# amp_interface_v_1_0.net
KiCad netlist of a schematic drawn in EAGLE
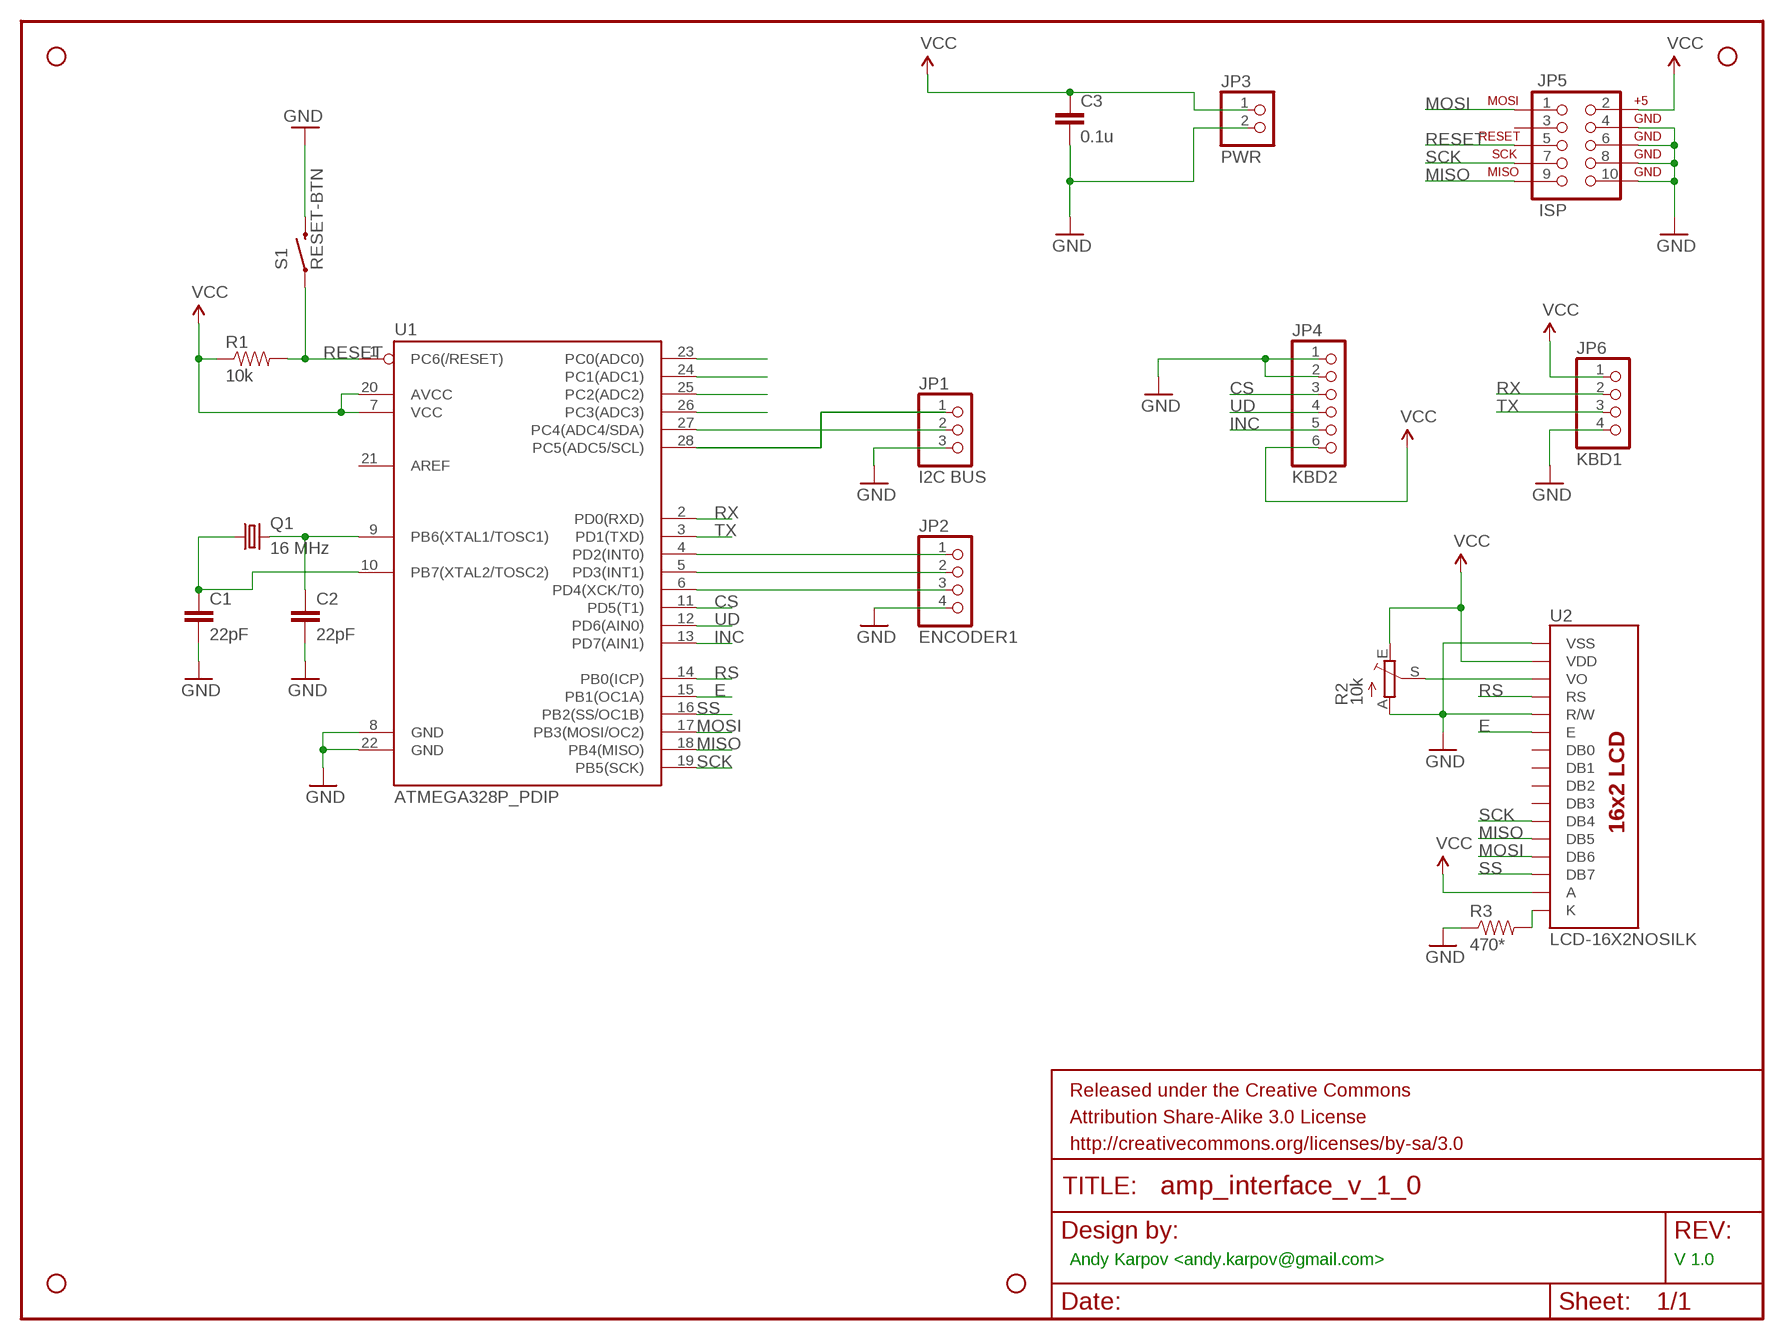
[diagram p0: schematic, sheet 1]

(export (version "E")
  (design (tool "Eeschema 10.0.6"))
  (components
    (comp (ref "C1")
      (value "22pF")
      (footprint "eagle-import:CAP-PTH-SMALL2")
      (libsource (lib "eagle-import") (part "CAPPTH2"))
    )
    (comp (ref "C2")
      (value "22pF")
      (footprint "eagle-import:CAP-PTH-SMALL2")
      (libsource (lib "eagle-import") (part "CAPPTH2"))
    )
    (comp (ref "C3")
      (value "0.1u")
      (footprint "eagle-import:CAP-PTH-SMALL2")
      (libsource (lib "eagle-import") (part "CAPPTH2"))
    )
    (comp (ref "FRAME1")
      (value "FRAME-LETTER")
      (footprint "eagle-import:CREATIVE_COMMONS")
      (libsource (lib "eagle-import") (part "FRAME-LETTER"))
    )
    (comp (ref "JP1")
      (value "I2C BUS")
      (footprint "eagle-import:1X03")
      (libsource (lib "eagle-import") (part "PINHD-1X3"))
    )
    (comp (ref "JP2")
      (value "ENCODER1")
      (footprint "eagle-import:1X04")
      (libsource (lib "eagle-import") (part "PINHD-1X4"))
    )
    (comp (ref "JP3")
      (value "PWR")
      (footprint "eagle-import:1X02")
      (libsource (lib "eagle-import") (part "PINHD-1X2"))
    )
    (comp (ref "JP4")
      (value "KBD2")
      (footprint "eagle-import:1X06")
      (libsource (lib "eagle-import") (part "PINHD-1X6"))
    )
    (comp (ref "JP5")
      (value "ISP")
      (footprint "eagle-import:2X5-SHROUDED")
      (libsource (lib "eagle-import") (part "AVR_SPI_PROG2PTH2"))
    )
    (comp (ref "JP6")
      (value "KBD1")
      (footprint "eagle-import:1X04")
      (libsource (lib "eagle-import") (part "PINHD-1X4"))
    )
    (comp (ref "Q1")
      (value "16 MHz")
      (footprint "eagle-import:HC49_S")
      (libsource (lib "eagle-import") (part "CRYSTALHC49S"))
    )
    (comp (ref "R1")
      (value "10k")
      (footprint "eagle-import:AXIAL-0.4")
      (libsource (lib "eagle-import") (part "RESISTORPTH-1/4W"))
    )
    (comp (ref "R2")
      (value "10k")
      (footprint "eagle-import:B64Y")
      (libsource (lib "eagle-import") (part "TRIM_EU-B64Y"))
    )
    (comp (ref "R3")
      (value "470*")
      (footprint "eagle-import:AXIAL-0.4")
      (libsource (lib "eagle-import") (part "RESISTORPTH-1/4W"))
    )
    (comp (ref "S1")
      (value "RESET-BTN")
      (footprint "eagle-import:TACTILE-PTH")
      (libsource (lib "eagle-import") (part "SWITCH-MOMENTARY-2PTH"))
    )
    (comp (ref "STANDOFF1")
      (value "STAND-OFF")
      (footprint "eagle-import:STAND-OFF")
      (libsource (lib "eagle-import") (part "STAND-OFF"))
    )
    (comp (ref "STANDOFF2")
      (value "STAND-OFF")
      (footprint "eagle-import:STAND-OFF")
      (libsource (lib "eagle-import") (part "STAND-OFF"))
    )
    (comp (ref "STANDOFF3")
      (value "STAND-OFF")
      (footprint "eagle-import:STAND-OFF")
      (libsource (lib "eagle-import") (part "STAND-OFF"))
    )
    (comp (ref "STANDOFF4")
      (value "STAND-OFF")
      (footprint "eagle-import:STAND-OFF")
      (libsource (lib "eagle-import") (part "STAND-OFF"))
    )
    (comp (ref "U1")
      (value "ATMEGA328P_PDIP")
      (footprint "eagle-import:DIL28-3")
      (libsource (lib "eagle-import") (part "ATMEGA328P_PDIP"))
    )
    (comp (ref "U2")
      (value "LCD-16X2NOSILK")
      (footprint "eagle-import:LCD-16X2_NOSILK")
      (libsource (lib "eagle-import") (part "LCD-16X2NOSILK"))
    )
  )
  (nets
    (net (code "1") (name "/CS") (class "Default")
      (node (ref "JP4") (pin "3") (pinfunction "3_3") (pintype "passive"))
      (node (ref "U1") (pin "11") (pinfunction "PD5(T1)_11") (pintype "bidirectional"))
    )
    (net (code "2") (name "/E") (class "Default")
      (node (ref "U1") (pin "15") (pinfunction "PB1(OC1A)_15") (pintype "bidirectional"))
      (node (ref "U2") (pin "6") (pinfunction "E_6") (pintype "input"))
    )
    (net (code "3") (name "/INC") (class "Default")
      (node (ref "JP4") (pin "5") (pinfunction "5_5") (pintype "passive"))
      (node (ref "U1") (pin "13") (pinfunction "PD7(AIN1)_13") (pintype "bidirectional"))
    )
    (net (code "4") (name "/MISO") (class "Default")
      (node (ref "JP5") (pin "9") (pinfunction "9_9") (pintype "passive"))
      (node (ref "U1") (pin "18") (pinfunction "PB4(MISO)_18") (pintype "bidirectional"))
      (node (ref "U2") (pin "12") (pinfunction "DB5_12") (pintype "bidirectional"))
    )
    (net (code "5") (name "/MOSI") (class "Default")
      (node (ref "JP5") (pin "1") (pinfunction "1_1") (pintype "passive"))
      (node (ref "U1") (pin "17") (pinfunction "PB3(MOSI/OC2)_17") (pintype "bidirectional"))
      (node (ref "U2") (pin "13") (pinfunction "DB6_13") (pintype "bidirectional"))
    )
    (net (code "6") (name "/RESET") (class "Default")
      (node (ref "JP5") (pin "5") (pinfunction "5_5") (pintype "passive"))
      (node (ref "R1") (pin "P$2") (pinfunction "2_P$2") (pintype "passive"))
      (node (ref "S1") (pin "1") (pinfunction "1_1") (pintype "passive"))
      (node (ref "U1") (pin "1") (pinfunction "PC6(/RESET)_1") (pintype "bidirectional"))
    )
    (net (code "7") (name "/RS") (class "Default")
      (node (ref "U1") (pin "14") (pinfunction "PB0(ICP)_14") (pintype "bidirectional"))
      (node (ref "U2") (pin "4") (pinfunction "RS_4") (pintype "input"))
    )
    (net (code "8") (name "/RX") (class "Default")
      (node (ref "JP6") (pin "2") (pinfunction "2_2") (pintype "passive"))
      (node (ref "U1") (pin "2") (pinfunction "PD0(RXD)_2") (pintype "bidirectional"))
    )
    (net (code "9") (name "/SCK") (class "Default")
      (node (ref "JP5") (pin "7") (pinfunction "7_7") (pintype "passive"))
      (node (ref "U1") (pin "19") (pinfunction "PB5(SCK)_19") (pintype "bidirectional"))
      (node (ref "U2") (pin "11") (pinfunction "DB4_11") (pintype "bidirectional"))
    )
    (net (code "10") (name "/SS") (class "Default")
      (node (ref "U1") (pin "16") (pinfunction "PB2(SS/OC1B)_16") (pintype "bidirectional"))
      (node (ref "U2") (pin "14") (pinfunction "DB7_14") (pintype "bidirectional"))
    )
    (net (code "11") (name "/TX") (class "Default")
      (node (ref "JP6") (pin "3") (pinfunction "3_3") (pintype "passive"))
      (node (ref "U1") (pin "3") (pinfunction "PD1(TXD)_3") (pintype "bidirectional"))
    )
    (net (code "12") (name "/UD") (class "Default")
      (node (ref "JP4") (pin "4") (pinfunction "4_4") (pintype "passive"))
      (node (ref "U1") (pin "12") (pinfunction "PD6(AIN0)_12") (pintype "bidirectional"))
    )
    (net (code "13") (name "GND") (class "Default")
      (node (ref "C1") (pin "2") (pinfunction "2_2") (pintype "passive"))
      (node (ref "C2") (pin "2") (pinfunction "2_2") (pintype "passive"))
      (node (ref "C3") (pin "2") (pinfunction "2_2") (pintype "passive"))
      (node (ref "JP1") (pin "3") (pinfunction "3_3") (pintype "passive"))
      (node (ref "JP2") (pin "4") (pinfunction "4_4") (pintype "passive"))
      (node (ref "JP3") (pin "2") (pinfunction "2_2") (pintype "passive"))
      (node (ref "JP4") (pin "1") (pinfunction "1_1") (pintype "passive"))
      (node (ref "JP4") (pin "2") (pinfunction "2_2") (pintype "passive"))
      (node (ref "JP5") (pin "10") (pinfunction "10_10") (pintype "passive"))
      (node (ref "JP5") (pin "4") (pinfunction "4_4") (pintype "passive"))
      (node (ref "JP5") (pin "6") (pinfunction "6_6") (pintype "passive"))
      (node (ref "JP5") (pin "8") (pinfunction "8_8") (pintype "passive"))
      (node (ref "JP6") (pin "4") (pinfunction "4_4") (pintype "passive"))
      (node (ref "R2") (pin "A") (pinfunction "A_A") (pintype "passive"))
      (node (ref "R3") (pin "P$1") (pinfunction "1_P$1") (pintype "passive"))
      (node (ref "S1") (pin "3") (pinfunction "2_3") (pintype "passive"))
      (node (ref "U1") (pin "22") (pinfunction "GND_22") (pintype "bidirectional"))
      (node (ref "U1") (pin "8") (pinfunction "GND_8") (pintype "bidirectional"))
      (node (ref "U2") (pin "1") (pinfunction "VSS_1") (pintype "power_in"))
      (node (ref "U2") (pin "5") (pinfunction "R/W_5") (pintype "input"))
    )
    (net (code "14") (name "Net-(R3-2)") (class "Default")
      (node (ref "R3") (pin "P$2") (pinfunction "2_P$2") (pintype "passive"))
      (node (ref "U2") (pin "16") (pinfunction "K_16") (pintype "power_in"))
    )
    (net (code "15") (name "Net-(U1-PB6(XTAL1{slash}TOSC1))") (class "Default")
      (node (ref "C2") (pin "1") (pinfunction "1_1") (pintype "passive"))
      (node (ref "Q1") (pin "2") (pinfunction "2_2") (pintype "passive"))
      (node (ref "U1") (pin "9") (pinfunction "PB6(XTAL1/TOSC1)_9") (pintype "bidirectional"))
    )
    (net (code "16") (name "Net-(U1-PB7(XTAL2{slash}TOSC2))") (class "Default")
      (node (ref "C1") (pin "1") (pinfunction "1_1") (pintype "passive"))
      (node (ref "Q1") (pin "1") (pinfunction "1_1") (pintype "passive"))
      (node (ref "U1") (pin "10") (pinfunction "PB7(XTAL2/TOSC2)_10") (pintype "bidirectional"))
    )
    (net (code "17") (name "Net-(U1-PC4(ADC4{slash}SDA))") (class "Default")
      (node (ref "JP1") (pin "2") (pinfunction "2_2") (pintype "passive"))
      (node (ref "U1") (pin "27") (pinfunction "PC4(ADC4/SDA)_27") (pintype "bidirectional"))
    )
    (net (code "18") (name "Net-(U1-PC5(ADC5{slash}SCL))") (class "Default")
      (node (ref "JP1") (pin "1") (pinfunction "1_1") (pintype "passive"))
      (node (ref "U1") (pin "28") (pinfunction "PC5(ADC5/SCL)_28") (pintype "bidirectional"))
    )
    (net (code "19") (name "Net-(U1-PD2(INT0))") (class "Default")
      (node (ref "JP2") (pin "1") (pinfunction "1_1") (pintype "passive"))
      (node (ref "U1") (pin "4") (pinfunction "PD2(INT0)_4") (pintype "bidirectional"))
    )
    (net (code "20") (name "Net-(U1-PD3(INT1))") (class "Default")
      (node (ref "JP2") (pin "2") (pinfunction "2_2") (pintype "passive"))
      (node (ref "U1") (pin "5") (pinfunction "PD3(INT1)_5") (pintype "bidirectional"))
    )
    (net (code "21") (name "Net-(U1-PD4(XCK{slash}T0))") (class "Default")
      (node (ref "JP2") (pin "3") (pinfunction "3_3") (pintype "passive"))
      (node (ref "U1") (pin "6") (pinfunction "PD4(XCK/T0)_6") (pintype "bidirectional"))
    )
    (net (code "22") (name "Net-(U2-VO)") (class "Default")
      (node (ref "R2") (pin "S") (pinfunction "S_S") (pintype "passive"))
      (node (ref "U2") (pin "3") (pinfunction "VO_3") (pintype "bidirectional"))
    )
    (net (code "23") (name "VCC") (class "Default")
      (node (ref "C3") (pin "1") (pinfunction "1_1") (pintype "passive"))
      (node (ref "JP3") (pin "1") (pinfunction "1_1") (pintype "passive"))
      (node (ref "JP4") (pin "6") (pinfunction "6_6") (pintype "passive"))
      (node (ref "JP5") (pin "2") (pinfunction "2_2") (pintype "passive"))
      (node (ref "JP6") (pin "1") (pinfunction "1_1") (pintype "passive"))
      (node (ref "R1") (pin "P$1") (pinfunction "1_P$1") (pintype "passive"))
      (node (ref "R2") (pin "E") (pinfunction "E_E") (pintype "passive"))
      (node (ref "U1") (pin "20") (pinfunction "AVCC_20") (pintype "bidirectional"))
      (node (ref "U1") (pin "7") (pinfunction "VCC_7") (pintype "bidirectional"))
      (node (ref "U2") (pin "15") (pinfunction "A_15") (pintype "power_in"))
      (node (ref "U2") (pin "2") (pinfunction "VDD_2") (pintype "power_in"))
    )
    (net (code "24") (name "unconnected-(JP5-Pad3)") (class "Default")
      (node (ref "JP5") (pin "3") (pinfunction "3_3") (pintype "passive"))
    )
    (net (code "25") (name "unconnected-(U1-AREF-Pad21)") (class "Default")
      (node (ref "U1") (pin "21") (pinfunction "AREF_21") (pintype "bidirectional"))
    )
    (net (code "26") (name "unconnected-(U1-PC0(ADC0)-Pad23)") (class "Default")
      (node (ref "U1") (pin "23") (pinfunction "PC0(ADC0)_23") (pintype "bidirectional"))
    )
    (net (code "27") (name "unconnected-(U1-PC1(ADC1)-Pad24)") (class "Default")
      (node (ref "U1") (pin "24") (pinfunction "PC1(ADC1)_24") (pintype "bidirectional"))
    )
    (net (code "28") (name "unconnected-(U1-PC2(ADC2)-Pad25)") (class "Default")
      (node (ref "U1") (pin "25") (pinfunction "PC2(ADC2)_25") (pintype "bidirectional"))
    )
    (net (code "29") (name "unconnected-(U1-PC3(ADC3)-Pad26)") (class "Default")
      (node (ref "U1") (pin "26") (pinfunction "PC3(ADC3)_26") (pintype "bidirectional"))
    )
    (net (code "30") (name "unconnected-(U2-DB0-Pad7)") (class "Default")
      (node (ref "U2") (pin "7") (pinfunction "DB0_7") (pintype "bidirectional"))
    )
    (net (code "31") (name "unconnected-(U2-DB1-Pad8)") (class "Default")
      (node (ref "U2") (pin "8") (pinfunction "DB1_8") (pintype "bidirectional"))
    )
    (net (code "32") (name "unconnected-(U2-DB2-Pad9)") (class "Default")
      (node (ref "U2") (pin "9") (pinfunction "DB2_9") (pintype "bidirectional"))
    )
    (net (code "33") (name "unconnected-(U2-DB3-Pad10)") (class "Default")
      (node (ref "U2") (pin "10") (pinfunction "DB3_10") (pintype "bidirectional"))
    )
  )
)
